# BumperDuino.net
KiCad netlist of a schematic drawn in EAGLE
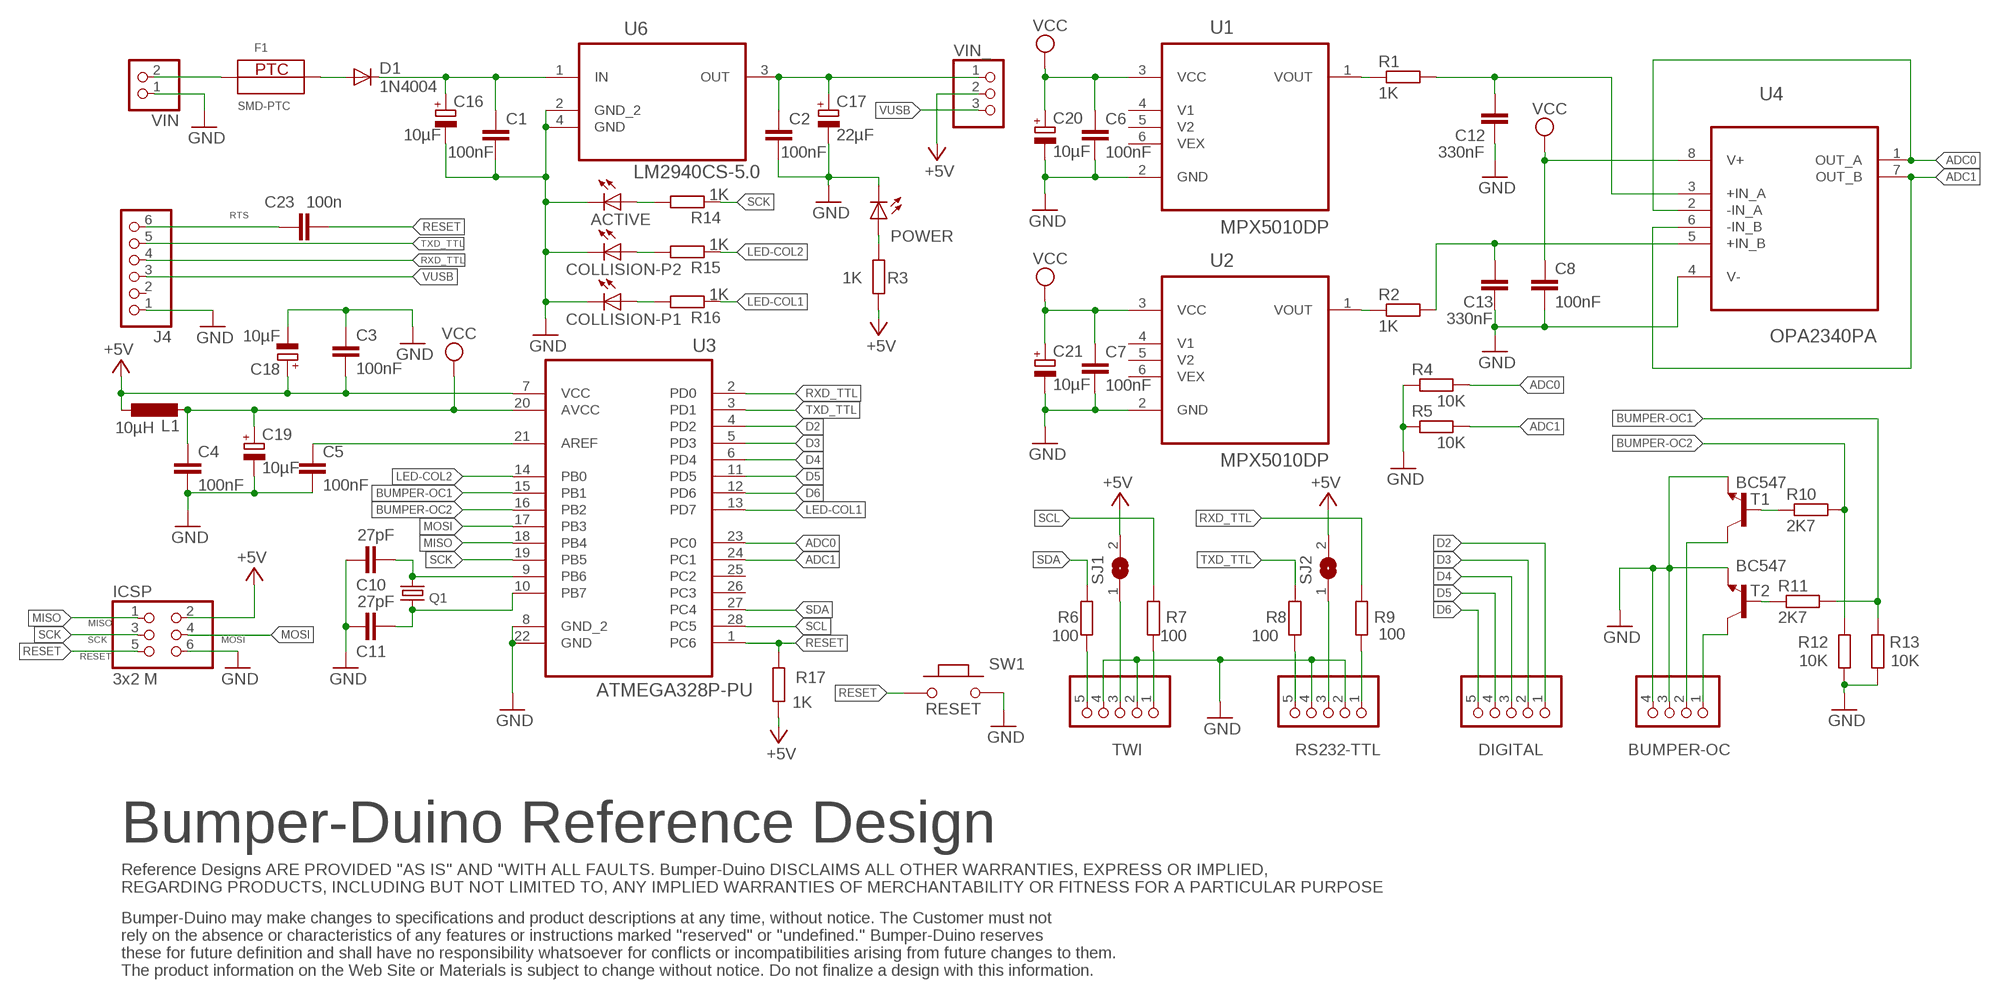
[diagram p0: schematic, sheet 1]

(export (version "E")
  (design (tool "Eeschema 10.0.6"))
  (components
    (comp (ref "ACTIVE")
      (value "LED3MM")
      (footprint "eagle-import:LED3MM")
      (libsource (lib "eagle-import") (part "LED3MM"))
    )
    (comp (ref "BUMPER-OC")
      (value "PINHD-1X4")
      (footprint "eagle-import:1X04")
      (libsource (lib "eagle-import") (part "PINHD-1X4"))
    )
    (comp (ref "C1")
      (value "100nF")
      (footprint "eagle-import:C025-025X050")
      (libsource (lib "eagle-import") (part "C-EU025-025X050"))
    )
    (comp (ref "C2")
      (value "100nF")
      (footprint "eagle-import:C025-025X050")
      (libsource (lib "eagle-import") (part "C-EU025-025X050"))
    )
    (comp (ref "C3")
      (value "100nF")
      (footprint "eagle-import:C025-025X050")
      (libsource (lib "eagle-import") (part "C-EU025-025X050"))
    )
    (comp (ref "C4")
      (value "100nF")
      (footprint "eagle-import:C025-025X050")
      (libsource (lib "eagle-import") (part "C-EU025-025X050"))
    )
    (comp (ref "C5")
      (value "100nF")
      (footprint "eagle-import:C025-025X050")
      (libsource (lib "eagle-import") (part "C-EU025-025X050"))
    )
    (comp (ref "C6")
      (value "100nF")
      (footprint "eagle-import:C025-025X050")
      (libsource (lib "eagle-import") (part "C-EU025-025X050"))
    )
    (comp (ref "C7")
      (value "100nF")
      (footprint "eagle-import:C025-025X050")
      (libsource (lib "eagle-import") (part "C-EU025-025X050"))
    )
    (comp (ref "C8")
      (value "100nF")
      (footprint "eagle-import:C025-025X050")
      (libsource (lib "eagle-import") (part "C-EU025-025X050"))
    )
    (comp (ref "C10")
      (value "27pF")
      (footprint "eagle-import:C025-025X050")
      (libsource (lib "eagle-import") (part "C-EU025-025X050"))
    )
    (comp (ref "C11")
      (value "27pF")
      (footprint "eagle-import:C025-025X050")
      (libsource (lib "eagle-import") (part "C-EU025-025X050"))
    )
    (comp (ref "C12")
      (value "330nF")
      (footprint "eagle-import:C025_050-035X075")
      (libsource (lib "eagle-import") (part "C-EU025_050-035X075"))
    )
    (comp (ref "C13")
      (value "330nF")
      (footprint "eagle-import:C025_050-035X075")
      (libsource (lib "eagle-import") (part "C-EU025_050-035X075"))
    )
    (comp (ref "C16")
      (value "10µF")
      (footprint "eagle-import:E2,5-5")
      (libsource (lib "eagle-import") (part "CPOL-EUE2.5-5"))
    )
    (comp (ref "C17")
      (value "22µF")
      (footprint "eagle-import:E2,5-5")
      (libsource (lib "eagle-import") (part "CPOL-EUE2.5-5"))
    )
    (comp (ref "C18")
      (value "10µF")
      (footprint "eagle-import:E2,5-5")
      (libsource (lib "eagle-import") (part "CPOL-EUE2.5-5"))
    )
    (comp (ref "C19")
      (value "10µF")
      (footprint "eagle-import:E2,5-5")
      (libsource (lib "eagle-import") (part "CPOL-EUE2.5-5"))
    )
    (comp (ref "C20")
      (value "10µF")
      (footprint "eagle-import:E2,5-5")
      (libsource (lib "eagle-import") (part "CPOL-EUE2.5-5"))
    )
    (comp (ref "C21")
      (value "10µF")
      (footprint "eagle-import:E2,5-5")
      (libsource (lib "eagle-import") (part "CPOL-EUE2.5-5"))
    )
    (comp (ref "C23")
      (value "100n")
      (footprint "eagle-import:C025-025X050")
      (libsource (lib "eagle-import") (part "C-EU025-025X050"))
    )
    (comp (ref "COLLISION-P1")
      (value "LED3MM")
      (footprint "eagle-import:LED3MM")
      (libsource (lib "eagle-import") (part "LED3MM"))
    )
    (comp (ref "COLLISION-P2")
      (value "LED3MM")
      (footprint "eagle-import:LED3MM")
      (libsource (lib "eagle-import") (part "LED3MM"))
    )
    (comp (ref "D1")
      (value "1N4004")
      (footprint "eagle-import:DO41-10")
      (libsource (lib "eagle-import") (part "1N4004"))
    )
    (comp (ref "DIGITAL")
      (value "PINHD-1X5")
      (footprint "eagle-import:1X05")
      (libsource (lib "eagle-import") (part "PINHD-1X5"))
    )
    (comp (ref "F1")
      (value "SMD-PTC")
      (footprint "eagle-import:SMD-PTC")
      (libsource (lib "eagle-import") (part "SMD-PTC"))
    )
    (comp (ref "ICSP")
      (value "3x2 M")
      (footprint "eagle-import:2X03")
      (libsource (lib "eagle-import") (part "PINHD-2X3"))
    )
    (comp (ref "J4")
      (value "6x1F Low profile (machined)")
      (footprint "eagle-import:1X06-TH")
      (libsource (lib "eagle-import") (part "PINHD-1X6TH"))
    )
    (comp (ref "L1")
      (value "10µH")
      (footprint "eagle-import:0204_7")
      (libsource (lib "eagle-import") (part "L-EU0204/7"))
    )
    (comp (ref "POWER")
      (value "LED3MM")
      (footprint "eagle-import:LED3MM")
      (libsource (lib "eagle-import") (part "LED3MM"))
    )
    (comp (ref "Q1")
      (value "HC49/S")
      (footprint "eagle-import:HC49_S")
      (libsource (lib "eagle-import") (part "HC49/S"))
    )
    (comp (ref "R1")
      (value "1K")
      (footprint "eagle-import:R1206")
      (libsource (lib "eagle-import") (part "R-EU_R1206"))
    )
    (comp (ref "R2")
      (value "1K")
      (footprint "eagle-import:R1206")
      (libsource (lib "eagle-import") (part "R-EU_R1206"))
    )
    (comp (ref "R3")
      (value "1K")
      (footprint "eagle-import:R1206")
      (libsource (lib "eagle-import") (part "R-EU_R1206"))
    )
    (comp (ref "R4")
      (value "10K")
      (footprint "eagle-import:R1206")
      (libsource (lib "eagle-import") (part "R-EU_R1206"))
    )
    (comp (ref "R5")
      (value "10K")
      (footprint "eagle-import:R1206")
      (libsource (lib "eagle-import") (part "R-EU_R1206"))
    )
    (comp (ref "R6")
      (value "100")
      (footprint "eagle-import:R1206")
      (libsource (lib "eagle-import") (part "R-EU_R1206"))
    )
    (comp (ref "R7")
      (value "100")
      (footprint "eagle-import:R1206")
      (libsource (lib "eagle-import") (part "R-EU_R1206"))
    )
    (comp (ref "R8")
      (value "100")
      (footprint "eagle-import:R1206")
      (libsource (lib "eagle-import") (part "R-EU_R1206"))
    )
    (comp (ref "R9")
      (value "100")
      (footprint "eagle-import:R1206")
      (libsource (lib "eagle-import") (part "R-EU_R1206"))
    )
    (comp (ref "R10")
      (value "2K7")
      (footprint "eagle-import:R1206")
      (libsource (lib "eagle-import") (part "R-EU_R1206"))
    )
    (comp (ref "R11")
      (value "2K7")
      (footprint "eagle-import:R1206")
      (libsource (lib "eagle-import") (part "R-EU_R1206"))
    )
    (comp (ref "R12")
      (value "10K")
      (footprint "eagle-import:R1206")
      (libsource (lib "eagle-import") (part "R-EU_R1206"))
    )
    (comp (ref "R13")
      (value "10K")
      (footprint "eagle-import:R1206")
      (libsource (lib "eagle-import") (part "R-EU_R1206"))
    )
    (comp (ref "R14")
      (value "1K")
      (footprint "eagle-import:R1206")
      (libsource (lib "eagle-import") (part "R-EU_R1206"))
    )
    (comp (ref "R15")
      (value "1K")
      (footprint "eagle-import:R1206")
      (libsource (lib "eagle-import") (part "R-EU_R1206"))
    )
    (comp (ref "R16")
      (value "1K")
      (footprint "eagle-import:R1206")
      (libsource (lib "eagle-import") (part "R-EU_R1206"))
    )
    (comp (ref "R17")
      (value "1K")
      (footprint "eagle-import:R1206")
      (libsource (lib "eagle-import") (part "R-EU_R1206"))
    )
    (comp (ref "RS232-TTL")
      (value "PINHD-1X5")
      (footprint "eagle-import:1X05")
      (libsource (lib "eagle-import") (part "PINHD-1X5"))
    )
    (comp (ref "SJ1")
      (value "SJW")
      (footprint "eagle-import:SJW")
      (libsource (lib "eagle-import") (part "SJW"))
    )
    (comp (ref "SJ2")
      (value "SJW")
      (footprint "eagle-import:SJW")
      (libsource (lib "eagle-import") (part "SJW"))
    )
    (comp (ref "SW1")
      (value "RESET")
      (footprint "eagle-import:157SW")
      (libsource (lib "eagle-import") (part "PB157"))
    )
    (comp (ref "T1")
      (value "BC547")
      (footprint "eagle-import:TO92")
      (libsource (lib "eagle-import") (part "BC547"))
    )
    (comp (ref "T2")
      (value "BC547")
      (footprint "eagle-import:TO92")
      (libsource (lib "eagle-import") (part "BC547"))
    )
    (comp (ref "TWI")
      (value "PINHD-1X5")
      (footprint "eagle-import:1X05")
      (libsource (lib "eagle-import") (part "PINHD-1X5"))
    )
    (comp (ref "U1")
      (value "MPX5010DP")
      (footprint "eagle-import:FREESCALE_CASE_867C-05")
      (libsource (lib "eagle-import") (part "MPX5010DP"))
    )
    (comp (ref "U2")
      (value "MPX5010DP")
      (footprint "eagle-import:FREESCALE_CASE_867C-05")
      (libsource (lib "eagle-import") (part "MPX5010DP"))
    )
    (comp (ref "U3")
      (value "ATMEGA328P-PU")
      (footprint "eagle-import:DIP254P762X457-28")
      (libsource (lib "eagle-import") (part "ATMEGA328P-PU"))
    )
    (comp (ref "U4")
      (value "OPA2340PA")
      (footprint "eagle-import:DIP254P762X508-8")
      (libsource (lib "eagle-import") (part "OPA2340PA"))
    )
    (comp (ref "U6")
      (value "LM2940CS-5.0")
      (footprint "eagle-import:TO254P1435X464-4N")
      (libsource (lib "eagle-import") (part "LM2940CS-5.0"))
    )
    (comp (ref "VIN")
      (value "PINHD-1X2")
      (footprint "eagle-import:1X02")
      (libsource (lib "eagle-import") (part "PINHD-1X2"))
    )
    (comp (ref "VIN_")
      (value "PINHD-1X3")
      (footprint "eagle-import:1X03")
      (libsource (lib "eagle-import") (part "PINHD-1X3"))
    )
  )
  (nets
    (net (code "1") (name "+5V") (class "Default")
      (node (ref "C18") (pin "+") (pinfunction "+_+") (pintype "passive"))
      (node (ref "C3") (pin "2") (pinfunction "2_2") (pintype "passive"))
      (node (ref "ICSP") (pin "2") (pinfunction "2_2") (pintype "passive"))
      (node (ref "L1") (pin "1") (pinfunction "1_1") (pintype "passive"))
      (node (ref "R17") (pin "1") (pinfunction "1_1") (pintype "passive"))
      (node (ref "R3") (pin "1") (pinfunction "1_1") (pintype "passive"))
      (node (ref "SJ1") (pin "2") (pinfunction "2_2") (pintype "passive"))
      (node (ref "SJ2") (pin "2") (pinfunction "2_2") (pintype "passive"))
      (node (ref "U3") (pin "7") (pinfunction "VCC_7") (pintype "power_in"))
      (node (ref "VIN_") (pin "2") (pinfunction "2_2") (pintype "passive"))
    )
    (net (code "2") (name "/RTS") (class "Default")
      (node (ref "C23") (pin "2") (pinfunction "2_2") (pintype "passive"))
      (node (ref "J4") (pin "6") (pinfunction "6_6") (pintype "passive"))
    )
    (net (code "3") (name "ADC0") (class "Default")
      (node (ref "R4") (pin "2") (pinfunction "2_2") (pintype "passive"))
      (node (ref "U3") (pin "23") (pinfunction "PC0_23") (pintype "bidirectional"))
      (node (ref "U4") (pin "1") (pinfunction "OUT_A_1") (pintype "output"))
      (node (ref "U4") (pin "2") (pinfunction "-IN_A_2") (pintype "input"))
    )
    (net (code "4") (name "ADC1") (class "Default")
      (node (ref "R5") (pin "2") (pinfunction "2_2") (pintype "passive"))
      (node (ref "U3") (pin "24") (pinfunction "PC1_24") (pintype "bidirectional"))
      (node (ref "U4") (pin "6") (pinfunction "-IN_B_6") (pintype "input"))
      (node (ref "U4") (pin "7") (pinfunction "OUT_B_7") (pintype "output"))
    )
    (net (code "5") (name "BUMPER-OC1") (class "Default")
      (node (ref "R11") (pin "2") (pinfunction "2_2") (pintype "passive"))
      (node (ref "R13") (pin "2") (pinfunction "2_2") (pintype "passive"))
      (node (ref "U3") (pin "15") (pinfunction "PB1_15") (pintype "bidirectional"))
    )
    (net (code "6") (name "BUMPER-OC2") (class "Default")
      (node (ref "R10") (pin "2") (pinfunction "2_2") (pintype "passive"))
      (node (ref "R12") (pin "2") (pinfunction "2_2") (pintype "passive"))
      (node (ref "U3") (pin "16") (pinfunction "PB2_16") (pintype "bidirectional"))
    )
    (net (code "7") (name "D2") (class "Default")
      (node (ref "DIGITAL") (pin "1") (pinfunction "1_1") (pintype "passive"))
      (node (ref "U3") (pin "4") (pinfunction "PD2_4") (pintype "bidirectional"))
    )
    (net (code "8") (name "D3") (class "Default")
      (node (ref "DIGITAL") (pin "2") (pinfunction "2_2") (pintype "passive"))
      (node (ref "U3") (pin "5") (pinfunction "PD3_5") (pintype "bidirectional"))
    )
    (net (code "9") (name "D4") (class "Default")
      (node (ref "DIGITAL") (pin "3") (pinfunction "3_3") (pintype "passive"))
      (node (ref "U3") (pin "6") (pinfunction "PD4_6") (pintype "bidirectional"))
    )
    (net (code "10") (name "D5") (class "Default")
      (node (ref "DIGITAL") (pin "4") (pinfunction "4_4") (pintype "passive"))
      (node (ref "U3") (pin "11") (pinfunction "PD5_11") (pintype "bidirectional"))
    )
    (net (code "11") (name "D6") (class "Default")
      (node (ref "DIGITAL") (pin "5") (pinfunction "5_5") (pintype "passive"))
      (node (ref "U3") (pin "12") (pinfunction "PD6_12") (pintype "bidirectional"))
    )
    (net (code "12") (name "GND") (class "Default")
      (node (ref "ACTIVE") (pin "K") (pinfunction "C_K") (pintype "passive"))
      (node (ref "BUMPER-OC") (pin "3") (pinfunction "3_3") (pintype "passive"))
      (node (ref "BUMPER-OC") (pin "4") (pinfunction "4_4") (pintype "passive"))
      (node (ref "C1") (pin "2") (pinfunction "2_2") (pintype "passive"))
      (node (ref "C10") (pin "1") (pinfunction "1_1") (pintype "passive"))
      (node (ref "C11") (pin "1") (pinfunction "1_1") (pintype "passive"))
      (node (ref "C12") (pin "2") (pinfunction "2_2") (pintype "passive"))
      (node (ref "C13") (pin "2") (pinfunction "2_2") (pintype "passive"))
      (node (ref "C16") (pin "-") (pinfunction "-_-") (pintype "passive"))
      (node (ref "C17") (pin "-") (pinfunction "-_-") (pintype "passive"))
      (node (ref "C18") (pin "-") (pinfunction "-_-") (pintype "passive"))
      (node (ref "C19") (pin "-") (pinfunction "-_-") (pintype "passive"))
      (node (ref "C2") (pin "2") (pinfunction "2_2") (pintype "passive"))
      (node (ref "C20") (pin "-") (pinfunction "-_-") (pintype "passive"))
      (node (ref "C21") (pin "-") (pinfunction "-_-") (pintype "passive"))
      (node (ref "C3") (pin "1") (pinfunction "1_1") (pintype "passive"))
      (node (ref "C4") (pin "2") (pinfunction "2_2") (pintype "passive"))
      (node (ref "C5") (pin "2") (pinfunction "2_2") (pintype "passive"))
      (node (ref "C6") (pin "2") (pinfunction "2_2") (pintype "passive"))
      (node (ref "C7") (pin "2") (pinfunction "2_2") (pintype "passive"))
      (node (ref "C8") (pin "2") (pinfunction "2_2") (pintype "passive"))
      (node (ref "COLLISION-P1") (pin "K") (pinfunction "C_K") (pintype "passive"))
      (node (ref "COLLISION-P2") (pin "K") (pinfunction "C_K") (pintype "passive"))
      (node (ref "ICSP") (pin "6") (pinfunction "6_6") (pintype "passive"))
      (node (ref "J4") (pin "1") (pinfunction "1_1") (pintype "passive"))
      (node (ref "POWER") (pin "K") (pinfunction "C_K") (pintype "passive"))
      (node (ref "R12") (pin "1") (pinfunction "1_1") (pintype "passive"))
      (node (ref "R13") (pin "1") (pinfunction "1_1") (pintype "passive"))
      (node (ref "R4") (pin "1") (pinfunction "1_1") (pintype "passive"))
      (node (ref "R5") (pin "1") (pinfunction "1_1") (pintype "passive"))
      (node (ref "RS232-TTL") (pin "2") (pinfunction "2_2") (pintype "passive"))
      (node (ref "RS232-TTL") (pin "4") (pinfunction "4_4") (pintype "passive"))
      (node (ref "SW1") (pin "2") (pinfunction "2_2") (pintype "passive"))
      (node (ref "T1") (pin "1") (pinfunction "E_1") (pintype "passive"))
      (node (ref "T2") (pin "1") (pinfunction "E_1") (pintype "passive"))
      (node (ref "TWI") (pin "2") (pinfunction "2_2") (pintype "passive"))
      (node (ref "TWI") (pin "4") (pinfunction "4_4") (pintype "passive"))
      (node (ref "U1") (pin "2") (pinfunction "GND_2") (pintype "power_in"))
      (node (ref "U2") (pin "2") (pinfunction "GND_2") (pintype "power_in"))
      (node (ref "U3") (pin "22") (pinfunction "GND_22") (pintype "passive"))
      (node (ref "U3") (pin "8") (pinfunction "GND_2_8") (pintype "passive"))
      (node (ref "U4") (pin "4") (pinfunction "V-_4") (pintype "power_in"))
      (node (ref "U6") (pin "2") (pinfunction "GND_2_2") (pintype "passive"))
      (node (ref "U6") (pin "4") (pinfunction "GND_4") (pintype "passive"))
      (node (ref "VIN") (pin "1") (pinfunction "1_1") (pintype "passive"))
    )
    (net (code "13") (name "LED-COL1") (class "Default")
      (node (ref "R16") (pin "1") (pinfunction "1_1") (pintype "passive"))
      (node (ref "U3") (pin "13") (pinfunction "PD7_13") (pintype "bidirectional"))
    )
    (net (code "14") (name "LED-COL2") (class "Default")
      (node (ref "R15") (pin "1") (pinfunction "1_1") (pintype "passive"))
      (node (ref "U3") (pin "14") (pinfunction "PB0_14") (pintype "bidirectional"))
    )
    (net (code "15") (name "MISO") (class "Default")
      (node (ref "ICSP") (pin "1") (pinfunction "1_1") (pintype "passive"))
      (node (ref "U3") (pin "18") (pinfunction "PB4_18") (pintype "bidirectional"))
    )
    (net (code "16") (name "MOSI") (class "Default")
      (node (ref "ICSP") (pin "4") (pinfunction "4_4") (pintype "passive"))
      (node (ref "U3") (pin "17") (pinfunction "PB3_17") (pintype "bidirectional"))
    )
    (net (code "17") (name "Net-(ACTIVE-PadA)") (class "Default")
      (node (ref "ACTIVE") (pin "A") (pinfunction "A_A") (pintype "passive"))
      (node (ref "R14") (pin "2") (pinfunction "2_2") (pintype "passive"))
    )
    (net (code "18") (name "Net-(COLLISION-P1-PadA)") (class "Default")
      (node (ref "COLLISION-P1") (pin "A") (pinfunction "A_A") (pintype "passive"))
      (node (ref "R16") (pin "2") (pinfunction "2_2") (pintype "passive"))
    )
    (net (code "19") (name "Net-(COLLISION-P2-PadA)") (class "Default")
      (node (ref "COLLISION-P2") (pin "A") (pinfunction "A_A") (pintype "passive"))
      (node (ref "R15") (pin "2") (pinfunction "2_2") (pintype "passive"))
    )
    (net (code "20") (name "Net-(D1-PadA)") (class "Default")
      (node (ref "D1") (pin "A") (pinfunction "A_A") (pintype "passive"))
      (node (ref "F1") (pin "2") (pinfunction "2_2") (pintype "bidirectional"))
    )
    (net (code "21") (name "Net-(F1-Pad1)") (class "Default")
      (node (ref "F1") (pin "1") (pinfunction "1_1") (pintype "bidirectional"))
      (node (ref "VIN") (pin "2") (pinfunction "2_2") (pintype "passive"))
    )
    (net (code "22") (name "Net-(POWER-PadA)") (class "Default")
      (node (ref "POWER") (pin "A") (pinfunction "A_A") (pintype "passive"))
      (node (ref "R3") (pin "2") (pinfunction "2_2") (pintype "passive"))
    )
    (net (code "23") (name "Net-(R6-Pad1)") (class "Default")
      (node (ref "R6") (pin "1") (pinfunction "1_1") (pintype "passive"))
      (node (ref "TWI") (pin "5") (pinfunction "5_5") (pintype "passive"))
    )
    (net (code "24") (name "Net-(R7-Pad1)") (class "Default")
      (node (ref "R7") (pin "1") (pinfunction "1_1") (pintype "passive"))
      (node (ref "TWI") (pin "1") (pinfunction "1_1") (pintype "passive"))
    )
    (net (code "25") (name "Net-(R8-Pad1)") (class "Default")
      (node (ref "R8") (pin "1") (pinfunction "1_1") (pintype "passive"))
      (node (ref "RS232-TTL") (pin "5") (pinfunction "5_5") (pintype "passive"))
    )
    (net (code "26") (name "Net-(R9-Pad1)") (class "Default")
      (node (ref "R9") (pin "1") (pinfunction "1_1") (pintype "passive"))
      (node (ref "RS232-TTL") (pin "1") (pinfunction "1_1") (pintype "passive"))
    )
    (net (code "27") (name "Net-(RS232-TTL-Pad3)") (class "Default")
      (node (ref "RS232-TTL") (pin "3") (pinfunction "3_3") (pintype "passive"))
      (node (ref "SJ2") (pin "1") (pinfunction "1_1") (pintype "passive"))
    )
    (net (code "28") (name "Net-(SJ1-Pad1)") (class "Default")
      (node (ref "SJ1") (pin "1") (pinfunction "1_1") (pintype "passive"))
      (node (ref "TWI") (pin "3") (pinfunction "3_3") (pintype "passive"))
    )
    (net (code "29") (name "Net-(T1-B)") (class "Default")
      (node (ref "R10") (pin "1") (pinfunction "1_1") (pintype "passive"))
      (node (ref "T1") (pin "2") (pinfunction "B_2") (pintype "passive"))
    )
    (net (code "30") (name "Net-(T1-C)") (class "Default")
      (node (ref "BUMPER-OC") (pin "2") (pinfunction "2_2") (pintype "passive"))
      (node (ref "T1") (pin "3") (pinfunction "C_3") (pintype "passive"))
    )
    (net (code "31") (name "Net-(T2-B)") (class "Default")
      (node (ref "R11") (pin "1") (pinfunction "1_1") (pintype "passive"))
      (node (ref "T2") (pin "2") (pinfunction "B_2") (pintype "passive"))
    )
    (net (code "32") (name "Net-(T2-C)") (class "Default")
      (node (ref "BUMPER-OC") (pin "1") (pinfunction "1_1") (pintype "passive"))
      (node (ref "T2") (pin "3") (pinfunction "C_3") (pintype "passive"))
    )
    (net (code "33") (name "Net-(U1-VOUT)") (class "Default")
      (node (ref "R1") (pin "1") (pinfunction "1_1") (pintype "passive"))
      (node (ref "U1") (pin "1") (pinfunction "VOUT_1") (pintype "output"))
    )
    (net (code "34") (name "Net-(U2-VOUT)") (class "Default")
      (node (ref "R2") (pin "1") (pinfunction "1_1") (pintype "passive"))
      (node (ref "U2") (pin "1") (pinfunction "VOUT_1") (pintype "output"))
    )
    (net (code "35") (name "Net-(U3-AREF)") (class "Default")
      (node (ref "C5") (pin "1") (pinfunction "1_1") (pintype "passive"))
      (node (ref "U3") (pin "21") (pinfunction "AREF_21") (pintype "input"))
    )
    (net (code "36") (name "Net-(U3-PB6)") (class "Default")
      (node (ref "C10") (pin "2") (pinfunction "2_2") (pintype "passive"))
      (node (ref "Q1") (pin "2") (pinfunction "2_2") (pintype "passive"))
      (node (ref "U3") (pin "9") (pinfunction "PB6_9") (pintype "bidirectional"))
    )
    (net (code "37") (name "Net-(U3-PB7)") (class "Default")
      (node (ref "C11") (pin "2") (pinfunction "2_2") (pintype "passive"))
      (node (ref "Q1") (pin "1") (pinfunction "1_1") (pintype "passive"))
      (node (ref "U3") (pin "10") (pinfunction "PB7_10") (pintype "bidirectional"))
    )
    (net (code "38") (name "Net-(U4-+IN_A)") (class "Default")
      (node (ref "C12") (pin "1") (pinfunction "1_1") (pintype "passive"))
      (node (ref "R1") (pin "2") (pinfunction "2_2") (pintype "passive"))
      (node (ref "U4") (pin "3") (pinfunction "+IN_A_3") (pintype "input"))
    )
    (net (code "39") (name "Net-(U4-+IN_B)") (class "Default")
      (node (ref "C13") (pin "1") (pinfunction "1_1") (pintype "passive"))
      (node (ref "R2") (pin "2") (pinfunction "2_2") (pintype "passive"))
      (node (ref "U4") (pin "5") (pinfunction "+IN_B_5") (pintype "input"))
    )
    (net (code "40") (name "Net-(U6-IN)") (class "Default")
      (node (ref "C1") (pin "1") (pinfunction "1_1") (pintype "passive"))
      (node (ref "C16") (pin "+") (pinfunction "+_+") (pintype "passive"))
      (node (ref "D1") (pin "C") (pinfunction "C_C") (pintype "passive"))
      (node (ref "U6") (pin "1") (pinfunction "IN_1") (pintype "input"))
    )
    (net (code "41") (name "Net-(U6-OUT)") (class "Default")
      (node (ref "C17") (pin "+") (pinfunction "+_+") (pintype "passive"))
      (node (ref "C2") (pin "1") (pinfunction "1_1") (pintype "passive"))
      (node (ref "U6") (pin "3") (pinfunction "OUT_3") (pintype "output"))
      (node (ref "VIN_") (pin "1") (pinfunction "1_1") (pintype "passive"))
    )
    (net (code "42") (name "RESET") (class "Default")
      (node (ref "C23") (pin "1") (pinfunction "1_1") (pintype "passive"))
      (node (ref "ICSP") (pin "5") (pinfunction "5_5") (pintype "passive"))
      (node (ref "R17") (pin "2") (pinfunction "2_2") (pintype "passive"))
      (node (ref "SW1") (pin "1") (pinfunction "1_1") (pintype "passive"))
      (node (ref "U3") (pin "1") (pinfunction "PC6_1") (pintype "bidirectional"))
    )
    (net (code "43") (name "RXD_TTL") (class "Default")
      (node (ref "J4") (pin "4") (pinfunction "4_4") (pintype "passive"))
      (node (ref "R9") (pin "2") (pinfunction "2_2") (pintype "passive"))
      (node (ref "U3") (pin "2") (pinfunction "PD0_2") (pintype "bidirectional"))
    )
    (net (code "44") (name "SCK") (class "Default")
      (node (ref "ICSP") (pin "3") (pinfunction "3_3") (pintype "passive"))
      (node (ref "R14") (pin "1") (pinfunction "1_1") (pintype "passive"))
      (node (ref "U3") (pin "19") (pinfunction "PB5_19") (pintype "bidirectional"))
    )
    (net (code "45") (name "SCL") (class "Default")
      (node (ref "R7") (pin "2") (pinfunction "2_2") (pintype "passive"))
      (node (ref "U3") (pin "28") (pinfunction "PC5_28") (pintype "bidirectional"))
    )
    (net (code "46") (name "SDA") (class "Default")
      (node (ref "R6") (pin "2") (pinfunction "2_2") (pintype "passive"))
      (node (ref "U3") (pin "27") (pinfunction "PC4_27") (pintype "bidirectional"))
    )
    (net (code "47") (name "TXD_TTL") (class "Default")
      (node (ref "J4") (pin "5") (pinfunction "5_5") (pintype "passive"))
      (node (ref "R8") (pin "2") (pinfunction "2_2") (pintype "passive"))
      (node (ref "U3") (pin "3") (pinfunction "PD1_3") (pintype "bidirectional"))
    )
    (net (code "48") (name "VCC") (class "Default")
      (node (ref "C19") (pin "+") (pinfunction "+_+") (pintype "passive"))
      (node (ref "C20") (pin "+") (pinfunction "+_+") (pintype "passive"))
      (node (ref "C21") (pin "+") (pinfunction "+_+") (pintype "passive"))
      (node (ref "C4") (pin "1") (pinfunction "1_1") (pintype "passive"))
      (node (ref "C6") (pin "1") (pinfunction "1_1") (pintype "passive"))
      (node (ref "C7") (pin "1") (pinfunction "1_1") (pintype "passive"))
      (node (ref "C8") (pin "1") (pinfunction "1_1") (pintype "passive"))
      (node (ref "L1") (pin "2") (pinfunction "2_2") (pintype "passive"))
      (node (ref "U1") (pin "3") (pinfunction "VCC_3") (pintype "power_in"))
      (node (ref "U2") (pin "3") (pinfunction "VCC_3") (pintype "power_in"))
      (node (ref "U3") (pin "20") (pinfunction "AVCC_20") (pintype "power_in"))
      (node (ref "U4") (pin "8") (pinfunction "V+_8") (pintype "power_in"))
    )
    (net (code "49") (name "VUSB") (class "Default")
      (node (ref "J4") (pin "3") (pinfunction "3_3") (pintype "passive"))
      (node (ref "VIN_") (pin "3") (pinfunction "3_3") (pintype "passive"))
    )
    (net (code "50") (name "unconnected-(J4-Pad2)") (class "Default")
      (node (ref "J4") (pin "2") (pinfunction "2_2") (pintype "passive"))
    )
    (net (code "51") (name "unconnected-(U1-V1-Pad4)") (class "Default")
      (node (ref "U1") (pin "4") (pinfunction "V1_4") (pintype "input"))
    )
    (net (code "52") (name "unconnected-(U1-V2-Pad5)") (class "Default")
      (node (ref "U1") (pin "5") (pinfunction "V2_5") (pintype "input"))
    )
    (net (code "53") (name "unconnected-(U1-VEX-Pad6)") (class "Default")
      (node (ref "U1") (pin "6") (pinfunction "VEX_6") (pintype "passive"))
    )
    (net (code "54") (name "unconnected-(U2-V1-Pad4)") (class "Default")
      (node (ref "U2") (pin "4") (pinfunction "V1_4") (pintype "input"))
    )
    (net (code "55") (name "unconnected-(U2-V2-Pad5)") (class "Default")
      (node (ref "U2") (pin "5") (pinfunction "V2_5") (pintype "input"))
    )
    (net (code "56") (name "unconnected-(U2-VEX-Pad6)") (class "Default")
      (node (ref "U2") (pin "6") (pinfunction "VEX_6") (pintype "passive"))
    )
    (net (code "57") (name "unconnected-(U3-PC2-Pad25)") (class "Default")
      (node (ref "U3") (pin "25") (pinfunction "PC2_25") (pintype "bidirectional"))
    )
    (net (code "58") (name "unconnected-(U3-PC3-Pad26)") (class "Default")
      (node (ref "U3") (pin "26") (pinfunction "PC3_26") (pintype "bidirectional"))
    )
  )
)
